# ESC_holder.net
KiCad netlist of a schematic drawn in EAGLE
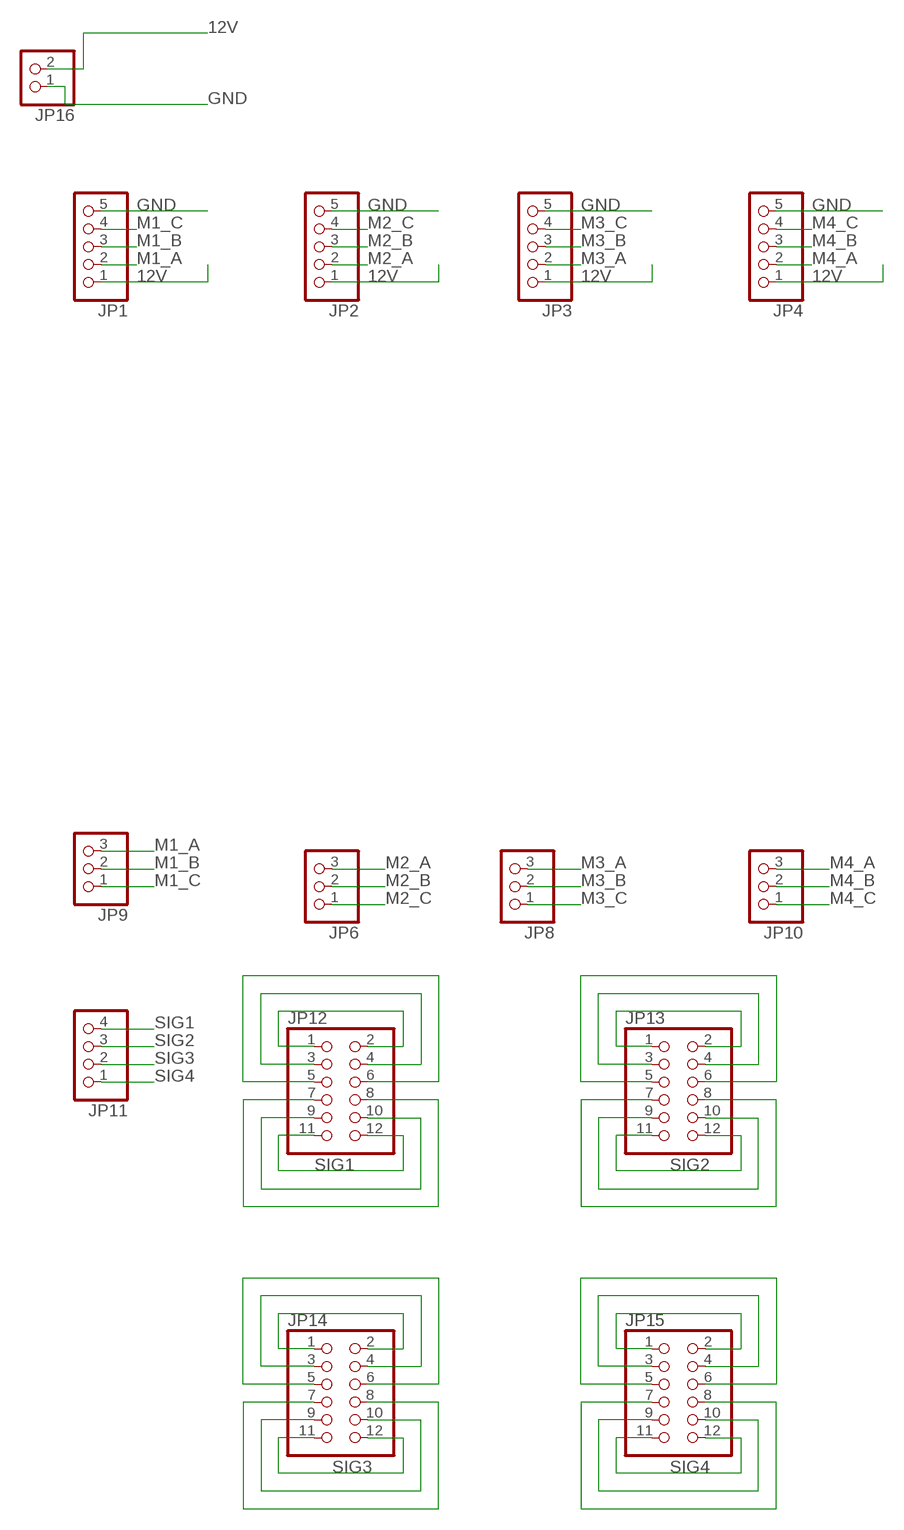
[diagram p0: schematic, sheet 1]

(export (version "E")
  (design (tool "Eeschema 10.0.6"))
  (components
    (comp (ref "JP1")
      (value "PINHD-1X5")
      (footprint "eagle-import:1X05")
      (libsource (lib "eagle-import") (part "PINHD-1X5"))
    )
    (comp (ref "JP2")
      (value "PINHD-1X5")
      (footprint "eagle-import:1X05")
      (libsource (lib "eagle-import") (part "PINHD-1X5"))
    )
    (comp (ref "JP3")
      (value "PINHD-1X5")
      (footprint "eagle-import:1X05")
      (libsource (lib "eagle-import") (part "PINHD-1X5"))
    )
    (comp (ref "JP4")
      (value "PINHD-1X5")
      (footprint "eagle-import:1X05")
      (libsource (lib "eagle-import") (part "PINHD-1X5"))
    )
    (comp (ref "JP6")
      (value "PINHD-1X3")
      (footprint "eagle-import:1X03")
      (libsource (lib "eagle-import") (part "PINHD-1X3"))
    )
    (comp (ref "JP8")
      (value "PINHD-1X3")
      (footprint "eagle-import:1X03")
      (libsource (lib "eagle-import") (part "PINHD-1X3"))
    )
    (comp (ref "JP9")
      (value "PINHD-1X3")
      (footprint "eagle-import:1X03")
      (libsource (lib "eagle-import") (part "PINHD-1X3"))
    )
    (comp (ref "JP10")
      (value "PINHD-1X3")
      (footprint "eagle-import:1X03")
      (libsource (lib "eagle-import") (part "PINHD-1X3"))
    )
    (comp (ref "JP11")
      (value "PINHD-1X4")
      (footprint "eagle-import:1X04")
      (libsource (lib "eagle-import") (part "PINHD-1X4"))
    )
    (comp (ref "JP12")
      (value "PINHD-2X6")
      (footprint "eagle-import:2X06")
      (libsource (lib "eagle-import") (part "PINHD-2X6"))
    )
    (comp (ref "JP13")
      (value "PINHD-2X6")
      (footprint "eagle-import:2X06")
      (libsource (lib "eagle-import") (part "PINHD-2X6"))
    )
    (comp (ref "JP14")
      (value "PINHD-2X6")
      (footprint "eagle-import:2X06")
      (libsource (lib "eagle-import") (part "PINHD-2X6"))
    )
    (comp (ref "JP15")
      (value "PINHD-2X6")
      (footprint "eagle-import:2X06")
      (libsource (lib "eagle-import") (part "PINHD-2X6"))
    )
    (comp (ref "JP16")
      (value "PINHD-1X2")
      (footprint "eagle-import:1X02")
      (libsource (lib "eagle-import") (part "PINHD-1X2"))
    )
  )
  (nets
    (net (code "1") (name "/12V") (class "Default")
      (node (ref "JP1") (pin "1") (pinfunction "1_1") (pintype "passive"))
      (node (ref "JP16") (pin "2") (pinfunction "2_2") (pintype "passive"))
      (node (ref "JP2") (pin "1") (pinfunction "1_1") (pintype "passive"))
      (node (ref "JP3") (pin "1") (pinfunction "1_1") (pintype "passive"))
      (node (ref "JP4") (pin "1") (pinfunction "1_1") (pintype "passive"))
    )
    (net (code "2") (name "/GND") (class "Default")
      (node (ref "JP1") (pin "5") (pinfunction "5_5") (pintype "passive"))
      (node (ref "JP16") (pin "1") (pinfunction "1_1") (pintype "passive"))
      (node (ref "JP2") (pin "5") (pinfunction "5_5") (pintype "passive"))
      (node (ref "JP3") (pin "5") (pinfunction "5_5") (pintype "passive"))
      (node (ref "JP4") (pin "5") (pinfunction "5_5") (pintype "passive"))
    )
    (net (code "3") (name "/M1_A") (class "Default")
      (node (ref "JP1") (pin "2") (pinfunction "2_2") (pintype "passive"))
      (node (ref "JP9") (pin "3") (pinfunction "3_3") (pintype "passive"))
    )
    (net (code "4") (name "/M1_B") (class "Default")
      (node (ref "JP1") (pin "3") (pinfunction "3_3") (pintype "passive"))
      (node (ref "JP9") (pin "2") (pinfunction "2_2") (pintype "passive"))
    )
    (net (code "5") (name "/M1_C") (class "Default")
      (node (ref "JP1") (pin "4") (pinfunction "4_4") (pintype "passive"))
      (node (ref "JP9") (pin "1") (pinfunction "1_1") (pintype "passive"))
    )
    (net (code "6") (name "/M2_A") (class "Default")
      (node (ref "JP2") (pin "2") (pinfunction "2_2") (pintype "passive"))
      (node (ref "JP6") (pin "3") (pinfunction "3_3") (pintype "passive"))
    )
    (net (code "7") (name "/M2_B") (class "Default")
      (node (ref "JP2") (pin "3") (pinfunction "3_3") (pintype "passive"))
      (node (ref "JP6") (pin "2") (pinfunction "2_2") (pintype "passive"))
    )
    (net (code "8") (name "/M2_C") (class "Default")
      (node (ref "JP2") (pin "4") (pinfunction "4_4") (pintype "passive"))
      (node (ref "JP6") (pin "1") (pinfunction "1_1") (pintype "passive"))
    )
    (net (code "9") (name "/M3_A") (class "Default")
      (node (ref "JP3") (pin "2") (pinfunction "2_2") (pintype "passive"))
      (node (ref "JP8") (pin "3") (pinfunction "3_3") (pintype "passive"))
    )
    (net (code "10") (name "/M3_B") (class "Default")
      (node (ref "JP3") (pin "3") (pinfunction "3_3") (pintype "passive"))
      (node (ref "JP8") (pin "2") (pinfunction "2_2") (pintype "passive"))
    )
    (net (code "11") (name "/M3_C") (class "Default")
      (node (ref "JP3") (pin "4") (pinfunction "4_4") (pintype "passive"))
      (node (ref "JP8") (pin "1") (pinfunction "1_1") (pintype "passive"))
    )
    (net (code "12") (name "/M4_A") (class "Default")
      (node (ref "JP10") (pin "3") (pinfunction "3_3") (pintype "passive"))
      (node (ref "JP4") (pin "2") (pinfunction "2_2") (pintype "passive"))
    )
    (net (code "13") (name "/M4_B") (class "Default")
      (node (ref "JP10") (pin "2") (pinfunction "2_2") (pintype "passive"))
      (node (ref "JP4") (pin "3") (pinfunction "3_3") (pintype "passive"))
    )
    (net (code "14") (name "/M4_C") (class "Default")
      (node (ref "JP10") (pin "1") (pinfunction "1_1") (pintype "passive"))
      (node (ref "JP4") (pin "4") (pinfunction "4_4") (pintype "passive"))
    )
    (net (code "15") (name "/SIG1") (class "Default")
      (node (ref "JP11") (pin "4") (pinfunction "4_4") (pintype "passive"))
      (node (ref "JP12") (pin "11") (pinfunction "11_11") (pintype "passive"))
      (node (ref "JP12") (pin "12") (pinfunction "12_12") (pintype "passive"))
    )
    (net (code "16") (name "/SIG2") (class "Default")
      (node (ref "JP11") (pin "3") (pinfunction "3_3") (pintype "passive"))
      (node (ref "JP13") (pin "11") (pinfunction "11_11") (pintype "passive"))
      (node (ref "JP13") (pin "12") (pinfunction "12_12") (pintype "passive"))
    )
    (net (code "17") (name "/SIG3") (class "Default")
      (node (ref "JP11") (pin "2") (pinfunction "2_2") (pintype "passive"))
      (node (ref "JP14") (pin "11") (pinfunction "11_11") (pintype "passive"))
      (node (ref "JP14") (pin "12") (pinfunction "12_12") (pintype "passive"))
    )
    (net (code "18") (name "/SIG4") (class "Default")
      (node (ref "JP11") (pin "1") (pinfunction "1_1") (pintype "passive"))
      (node (ref "JP15") (pin "11") (pinfunction "11_11") (pintype "passive"))
      (node (ref "JP15") (pin "12") (pinfunction "12_12") (pintype "passive"))
    )
    (net (code "19") (name "Net-(JP12-Pad1)") (class "Default")
      (node (ref "JP12") (pin "1") (pinfunction "1_1") (pintype "passive"))
      (node (ref "JP12") (pin "2") (pinfunction "2_2") (pintype "passive"))
    )
    (net (code "20") (name "Net-(JP12-Pad3)") (class "Default")
      (node (ref "JP12") (pin "3") (pinfunction "3_3") (pintype "passive"))
      (node (ref "JP12") (pin "4") (pinfunction "4_4") (pintype "passive"))
    )
    (net (code "21") (name "Net-(JP12-Pad5)") (class "Default")
      (node (ref "JP12") (pin "5") (pinfunction "5_5") (pintype "passive"))
      (node (ref "JP12") (pin "6") (pinfunction "6_6") (pintype "passive"))
    )
    (net (code "22") (name "Net-(JP12-Pad7)") (class "Default")
      (node (ref "JP12") (pin "7") (pinfunction "7_7") (pintype "passive"))
      (node (ref "JP12") (pin "8") (pinfunction "8_8") (pintype "passive"))
    )
    (net (code "23") (name "Net-(JP12-Pad10)") (class "Default")
      (node (ref "JP12") (pin "10") (pinfunction "10_10") (pintype "passive"))
      (node (ref "JP12") (pin "9") (pinfunction "9_9") (pintype "passive"))
    )
    (net (code "24") (name "Net-(JP13-Pad1)") (class "Default")
      (node (ref "JP13") (pin "1") (pinfunction "1_1") (pintype "passive"))
      (node (ref "JP13") (pin "2") (pinfunction "2_2") (pintype "passive"))
    )
    (net (code "25") (name "Net-(JP13-Pad3)") (class "Default")
      (node (ref "JP13") (pin "3") (pinfunction "3_3") (pintype "passive"))
      (node (ref "JP13") (pin "4") (pinfunction "4_4") (pintype "passive"))
    )
    (net (code "26") (name "Net-(JP13-Pad5)") (class "Default")
      (node (ref "JP13") (pin "5") (pinfunction "5_5") (pintype "passive"))
      (node (ref "JP13") (pin "6") (pinfunction "6_6") (pintype "passive"))
    )
    (net (code "27") (name "Net-(JP13-Pad7)") (class "Default")
      (node (ref "JP13") (pin "7") (pinfunction "7_7") (pintype "passive"))
      (node (ref "JP13") (pin "8") (pinfunction "8_8") (pintype "passive"))
    )
    (net (code "28") (name "Net-(JP13-Pad10)") (class "Default")
      (node (ref "JP13") (pin "10") (pinfunction "10_10") (pintype "passive"))
      (node (ref "JP13") (pin "9") (pinfunction "9_9") (pintype "passive"))
    )
    (net (code "29") (name "Net-(JP14-Pad1)") (class "Default")
      (node (ref "JP14") (pin "1") (pinfunction "1_1") (pintype "passive"))
      (node (ref "JP14") (pin "2") (pinfunction "2_2") (pintype "passive"))
    )
    (net (code "30") (name "Net-(JP14-Pad3)") (class "Default")
      (node (ref "JP14") (pin "3") (pinfunction "3_3") (pintype "passive"))
      (node (ref "JP14") (pin "4") (pinfunction "4_4") (pintype "passive"))
    )
    (net (code "31") (name "Net-(JP14-Pad5)") (class "Default")
      (node (ref "JP14") (pin "5") (pinfunction "5_5") (pintype "passive"))
      (node (ref "JP14") (pin "6") (pinfunction "6_6") (pintype "passive"))
    )
    (net (code "32") (name "Net-(JP14-Pad7)") (class "Default")
      (node (ref "JP14") (pin "7") (pinfunction "7_7") (pintype "passive"))
      (node (ref "JP14") (pin "8") (pinfunction "8_8") (pintype "passive"))
    )
    (net (code "33") (name "Net-(JP14-Pad10)") (class "Default")
      (node (ref "JP14") (pin "10") (pinfunction "10_10") (pintype "passive"))
      (node (ref "JP14") (pin "9") (pinfunction "9_9") (pintype "passive"))
    )
    (net (code "34") (name "Net-(JP15-Pad1)") (class "Default")
      (node (ref "JP15") (pin "1") (pinfunction "1_1") (pintype "passive"))
      (node (ref "JP15") (pin "2") (pinfunction "2_2") (pintype "passive"))
    )
    (net (code "35") (name "Net-(JP15-Pad3)") (class "Default")
      (node (ref "JP15") (pin "3") (pinfunction "3_3") (pintype "passive"))
      (node (ref "JP15") (pin "4") (pinfunction "4_4") (pintype "passive"))
    )
    (net (code "36") (name "Net-(JP15-Pad5)") (class "Default")
      (node (ref "JP15") (pin "5") (pinfunction "5_5") (pintype "passive"))
      (node (ref "JP15") (pin "6") (pinfunction "6_6") (pintype "passive"))
    )
    (net (code "37") (name "Net-(JP15-Pad7)") (class "Default")
      (node (ref "JP15") (pin "7") (pinfunction "7_7") (pintype "passive"))
      (node (ref "JP15") (pin "8") (pinfunction "8_8") (pintype "passive"))
    )
    (net (code "38") (name "Net-(JP15-Pad10)") (class "Default")
      (node (ref "JP15") (pin "10") (pinfunction "10_10") (pintype "passive"))
      (node (ref "JP15") (pin "9") (pinfunction "9_9") (pintype "passive"))
    )
  )
)
